# MCU_USB.net
KiCad netlist of a schematic drawn in Altium Designer
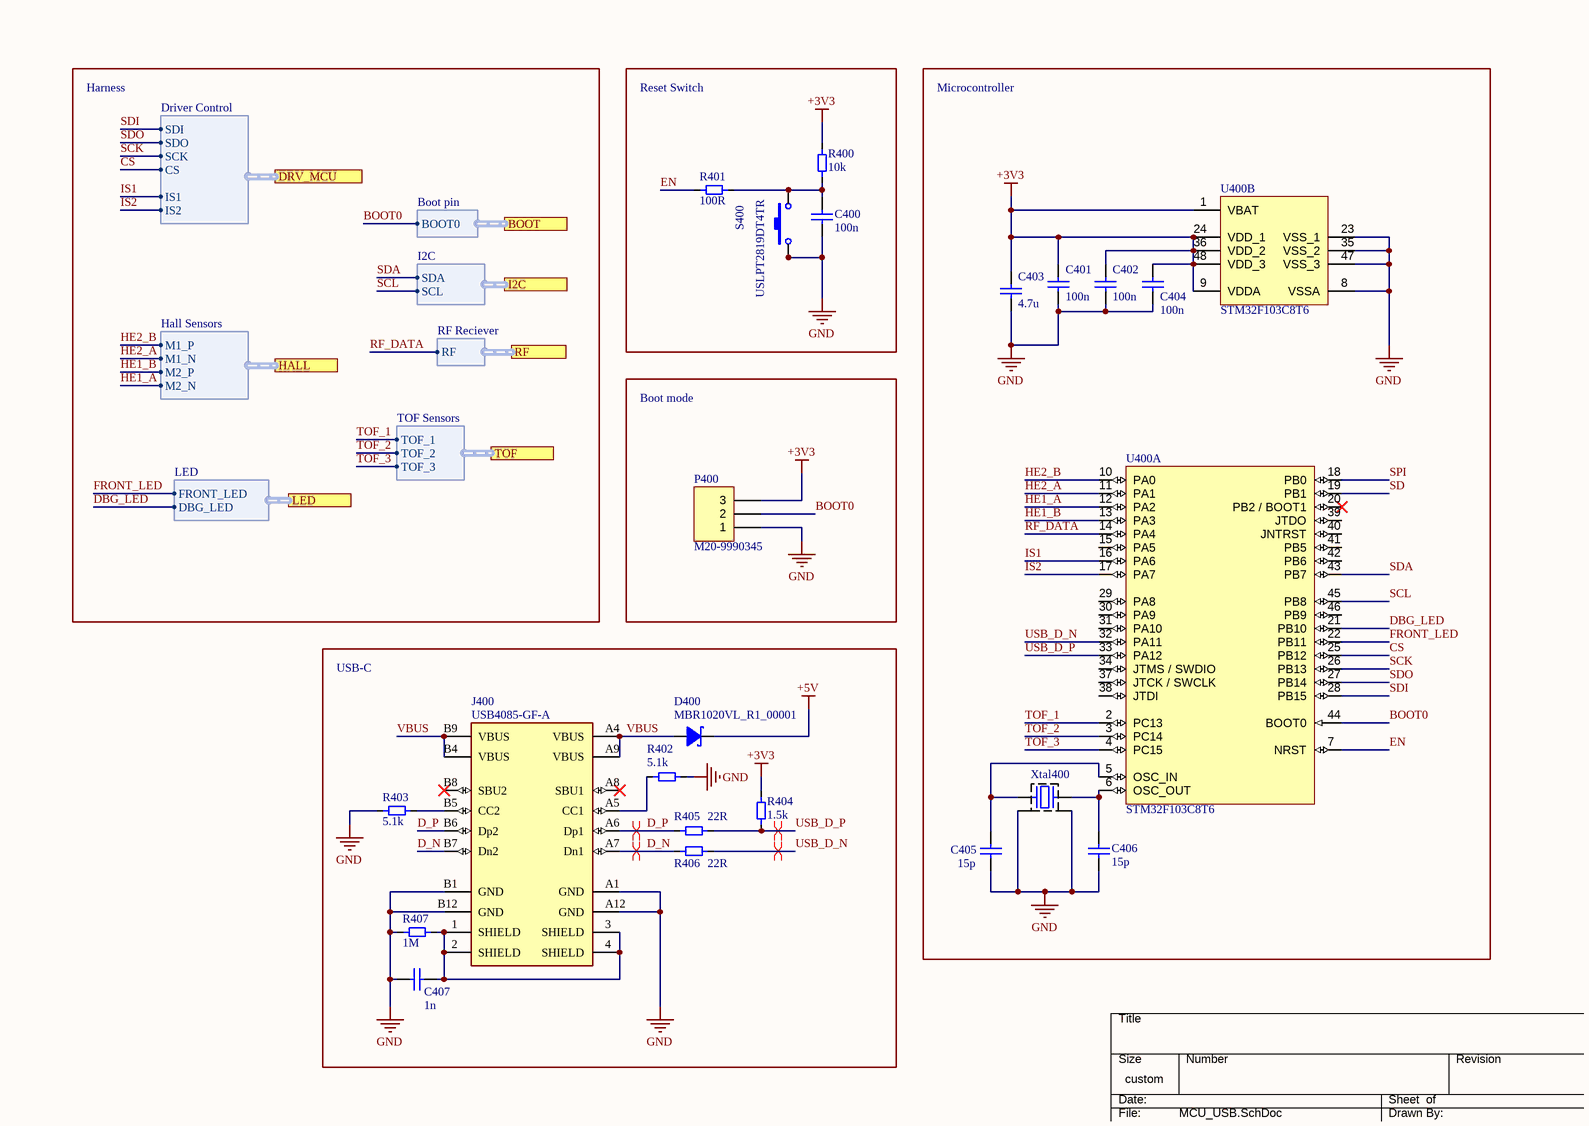
[diagram p0: MCU_USB.SchDoc]

(export (version "E")
  (design (tool "Eeschema 10.0.6"))
  (components
    (comp (ref "C400")
      (value "100n")
      (footprint "MLCC_0603_M")
      (description "MLCC, 0603, 100n, 10%, 50V, X7R")
      (fields (field (name "VOLTAGE") "50V") (field (name "TOLERANCE") "10%"))
      (libsource (lib "Krakul Vault") (part "CAPACITOR_NONPOL_IEC"))
    )
    (comp (ref "C401")
      (value "100n")
      (footprint "MLCC_0603_M")
      (description "MLCC, 0603, 100n, 10%, 50V, X7R")
      (fields (field (name "VOLTAGE") "50V") (field (name "TOLERANCE") "10%"))
      (libsource (lib "Krakul Vault") (part "CAPACITOR_NONPOL_IEC"))
    )
    (comp (ref "C402")
      (value "100n")
      (footprint "MLCC_0603_M")
      (description "MLCC, 0603, 100n, 10%, 50V, X7R")
      (fields (field (name "VOLTAGE") "50V") (field (name "TOLERANCE") "10%"))
      (libsource (lib "Krakul Vault") (part "CAPACITOR_NONPOL_IEC"))
    )
    (comp (ref "C403")
      (value "4.7u")
      (footprint "MLCC_0805_M")
      (description "MLCC, 0805, 4.7u, 20%, 50V, X5R")
      (fields (field (name "MANUFACTURER") "Any") (field (name "VOLTAGE") "50V"))
      (libsource (lib "Krakul Vault") (part "CAPACITOR_NONPOL_IEC"))
    )
    (comp (ref "C404")
      (value "100n")
      (footprint "MLCC_0603_M")
      (description "MLCC, 0603, 100n, 10%, 50V, X7R")
      (fields (field (name "VOLTAGE") "50V") (field (name "TOLERANCE") "10%"))
      (libsource (lib "Krakul Vault") (part "CAPACITOR_NONPOL_IEC"))
    )
    (comp (ref "C405")
      (value "15p")
      (footprint "MLCC_0402_M")
      (description "MLCC, 0402, 15p, 10%, 25V, C0G/NP0")
      (fields (field (name "MANUFACTURER") "Any") (field (name "TOLERANCE") "10%"))
      (libsource (lib "Krakul Vault") (part "CAPACITOR_NONPOL_IEC"))
    )
    (comp (ref "C406")
      (value "15p")
      (footprint "MLCC_0402_M")
      (description "MLCC, 0402, 15p, 10%, 25V, C0G/NP0")
      (fields (field (name "MANUFACTURER") "Any") (field (name "TOLERANCE") "10%"))
      (libsource (lib "Krakul Vault") (part "CAPACITOR_NONPOL_IEC"))
    )
    (comp (ref "C407")
      (value "1n")
      (footprint "MLCC_0603_M")
      (description "MLCC, 0603, 1n, 10%, 50V, X5R")
      (fields (field (name "MANUFACTURER") "Any") (field (name "TOLERANCE") "10%"))
      (libsource (lib "Krakul Vault") (part "CAPACITOR_NONPOL_IEC"))
    )
    (comp (ref "D400")
      (value "MBR1020VL_R1_00001")
      (footprint "FP-MBR1020VL_R1_00001-MFG")
      (description "Rectifier Diode, Schottky, 1 Phase, 1 Element, 1A, 20V V(RRM), Silicon")
      (fields (field (name "MANUFACTURER") "Panjit"))
      (libsource (lib "Krakul Vault") (part "Schottky generic 2 pins"))
    )
    (comp (ref "J400")
      (value "USB4085-GF-A")
      (footprint "FP-USB4085-GF-A-MFG")
      (description "USB Connector, 16 Contact(s), Female, Right Angle, Solder Terminal, Locking, Receptacle")
      (fields (field (name "MANUFACTURER") "GCT") (field (name "PART NUMBER") "USB4800-03-A"))
      (libsource (lib "Krakul Vault") (part "USB4085-GF-A"))
    )
    (comp (ref "P400")
      (value "M20-9990345")
      (footprint "3Pos Pin Header")
      (description "Connector Header Through Hole 3 position 0.100\" (2.54mm)")
      (fields (field (name "MANUFACTURER") "Harwin Inc."))
      (libsource (lib "Krakul Vault") (part "3 pin header"))
    )
    (comp (ref "R400")
      (value "10k")
      (footprint "Resistor_0603_M")
      (description "Resistor, 0603, 10k, 1%, 1/10W")
      (fields (field (name "MANUFACTURER") "Any") (field (name "TOLERANCE") "1%"))
      (libsource (lib "Krakul Vault") (part "RESISTOR_GENERIC_IEC"))
    )
    (comp (ref "R401")
      (value "100R")
      (footprint "Resistor_0603_M")
      (description "Resistor, 0603, 100R, 1%, 1/10W")
      (fields (field (name "POWER") "100mW") (field (name "MANUFACTURER") "Any"))
      (libsource (lib "Krakul Vault") (part "RESISTOR_GENERIC_IEC"))
    )
    (comp (ref "R402")
      (value "5.1k")
      (footprint "Resistor_0603_M")
      (description "Resistor, 0603, 5.1k, 1%, 1/10W")
      (fields (field (name "POWER") "100mW") (field (name "MANUFACTURER") "Any"))
      (libsource (lib "Krakul Vault") (part "RESISTOR_GENERIC_IEC"))
    )
    (comp (ref "R403")
      (value "5.1k")
      (footprint "Resistor_0603_M")
      (description "Resistor, 0603, 5.1k, 1%, 1/10W")
      (fields (field (name "POWER") "100mW") (field (name "MANUFACTURER") "Any"))
      (libsource (lib "Krakul Vault") (part "RESISTOR_GENERIC_IEC"))
    )
    (comp (ref "R404")
      (value "1.5k")
      (footprint "Resistor_0603_M")
      (description "Resistor, 0603, 1.5k, 1%, 1/10W")
      (fields (field (name "MANUFACTURER") "Any") (field (name "POWER") "100mW"))
      (libsource (lib "Krakul Vault") (part "RESISTOR_GENERIC_IEC"))
    )
    (comp (ref "R405")
      (value "22R")
      (footprint "Resistor_0603_M")
      (description "Resistor, 0603, 22R, 1%, 1/10W")
      (fields (field (name "TOLERANCE") "1%") (field (name "MANUFACTURER") "Any"))
      (libsource (lib "Krakul Vault") (part "RESISTOR_GENERIC_IEC"))
    )
    (comp (ref "R406")
      (value "22R")
      (footprint "Resistor_0603_M")
      (description "Resistor, 0603, 22R, 1%, 1/10W")
      (fields (field (name "TOLERANCE") "1%") (field (name "MANUFACTURER") "Any"))
      (libsource (lib "Krakul Vault") (part "RESISTOR_GENERIC_IEC"))
    )
    (comp (ref "R407")
      (value "1M")
      (footprint "Resistor_1206_M")
      (description "Resistor, 1206, 1M, 1%, 1/4W")
      (fields (field (name "MANUFACTURER") "Any"))
      (libsource (lib "Krakul Vault") (part "RESISTOR_GENERIC_IEC"))
    )
    (comp (ref "S400")
      (value "USLPT2819DT4TR")
      (footprint "USLPT2819DT4TR-Footprint-1")
      (description "Keypad Switch, SPST, 0.05A, 1.96N, Solder Terminal, Panel Mount")
      (fields (field (name "MANUFACTURER") "TE Connectivity ALCOSWITCH Switches"))
      (libsource (lib "Krakul Vault") (part "Copy of Switch 4-pin"))
    )
    (comp (ref "U400")
      (value "STM32F103C8T6")
      (footprint "STM-LQFP48_M")
      (description "MCU 32-bit STM32F1 ARM Cortex M3 RISC 64KB Flash 2.5V/3.3V 48-Pin LQFP Tray")
      (fields (field (name "MANUFACTURER") "STMicroelectronics"))
      (libsource (lib "Krakul Vault") (part "MC-ARM-STM32F103X4_6-SQ48"))
    )
    (comp (ref "Xtal400")
      (value "ABM11-16.000MHZ-12-N1G-T")
      (footprint "FP-ABM11-MFG")
      (description "Crystal 16MHz ±10ppm (Tol) ±15ppm (Stability) 12pF FUND 150Ohm 4-Pin Ultra Mini-CSMD T/R")
      (fields (field (name "MANUFACTURER") "Abracon LLC") (field (name "TOLERANCE") "0.001%"))
      (libsource (lib "Krakul Vault") (part "Crystal 4 pins"))
    )
  )
  (nets
    (net (code "12") (name "+3V3") (class "Default")
      (node (ref "C401") (pin "1") (pinfunction "1_1") (pintype "passive"))
      (node (ref "C402") (pin "1") (pinfunction "1_1") (pintype "passive"))
      (node (ref "C403") (pin "2") (pinfunction "2_2") (pintype "passive"))
      (node (ref "C404") (pin "1") (pinfunction "1_1") (pintype "passive"))
      (node (ref "P400") (pin "3") (pinfunction "3_3") (pintype "passive"))
      (node (ref "R400") (pin "2") (pinfunction "2_2") (pintype "passive"))
      (node (ref "R404") (pin "2") (pinfunction "2_2") (pintype "passive"))
      (node (ref "U400") (pin "1") (pinfunction "VBAT_1") (pintype "power_in"))
      (node (ref "U400") (pin "24") (pinfunction "VDD_1_24") (pintype "power_in"))
      (node (ref "U400") (pin "36") (pinfunction "VDD_2_36") (pintype "power_in"))
      (node (ref "U400") (pin "48") (pinfunction "VDD_3_48") (pintype "power_in"))
      (node (ref "U400") (pin "9") (pinfunction "VDDA_9") (pintype "power_in"))
    )
    (net (code "13") (name "+5V") (class "Default")
      (node (ref "D400") (pin "1") (pinfunction "C_1") (pintype "passive"))
    )
    (net (code "14") (name "/BOOT0") (class "Default")
      (node (ref "P400") (pin "2") (pinfunction "2_2") (pintype "passive"))
      (node (ref "U400") (pin "44") (pinfunction "BOOT0_44") (pintype "input"))
    )
    (net (code "15") (name "/CS") (class "Default")
      (node (ref "U400") (pin "25") (pinfunction "PB12_25") (pintype "bidirectional"))
    )
    (net (code "16") (name "/DBG_LED") (class "Default")
      (node (ref "U400") (pin "21") (pinfunction "PB10_21") (pintype "bidirectional"))
    )
    (net (code "17") (name "/D_N") (class "Default")
      (node (ref "J400") (pin "A7") (pinfunction "Dn1_A7") (pintype "bidirectional"))
      (node (ref "J400") (pin "B7") (pinfunction "Dn2_B7") (pintype "bidirectional"))
      (node (ref "R406") (pin "1") (pinfunction "1_1") (pintype "passive"))
    )
    (net (code "18") (name "/D_P") (class "Default")
      (node (ref "J400") (pin "A6") (pinfunction "Dp1_A6") (pintype "bidirectional"))
      (node (ref "J400") (pin "B6") (pinfunction "Dp2_B6") (pintype "bidirectional"))
      (node (ref "R405") (pin "1") (pinfunction "1_1") (pintype "passive"))
    )
    (net (code "19") (name "/EN") (class "Default")
      (node (ref "R401") (pin "2") (pinfunction "2_2") (pintype "passive"))
      (node (ref "U400") (pin "7") (pinfunction "NRST_7") (pintype "bidirectional"))
    )
    (net (code "20") (name "/FRONT_LED") (class "Default")
      (node (ref "U400") (pin "22") (pinfunction "PB11_22") (pintype "bidirectional"))
    )
    (net (code "21") (name "/HE1_A") (class "Default")
      (node (ref "U400") (pin "12") (pinfunction "PA2_12") (pintype "bidirectional"))
    )
    (net (code "22") (name "/HE1_B") (class "Default")
      (node (ref "U400") (pin "13") (pinfunction "PA3_13") (pintype "bidirectional"))
    )
    (net (code "23") (name "/HE2_A") (class "Default")
      (node (ref "U400") (pin "11") (pinfunction "PA1_11") (pintype "bidirectional"))
    )
    (net (code "24") (name "/HE2_B") (class "Default")
      (node (ref "U400") (pin "10") (pinfunction "PA0_10") (pintype "bidirectional"))
    )
    (net (code "25") (name "/IS1") (class "Default")
      (node (ref "U400") (pin "16") (pinfunction "PA6_16") (pintype "bidirectional"))
    )
    (net (code "26") (name "/IS2") (class "Default")
      (node (ref "U400") (pin "17") (pinfunction "PA7_17") (pintype "bidirectional"))
    )
    (net (code "27") (name "/RF_DATA") (class "Default")
      (node (ref "U400") (pin "14") (pinfunction "PA4_14") (pintype "bidirectional"))
    )
    (net (code "28") (name "/SCK") (class "Default")
      (node (ref "U400") (pin "26") (pinfunction "PB13_26") (pintype "bidirectional"))
    )
    (net (code "29") (name "/SCL") (class "Default")
      (node (ref "U400") (pin "45") (pinfunction "PB8_45") (pintype "bidirectional"))
    )
    (net (code "30") (name "/SD") (class "Default")
      (node (ref "U400") (pin "19") (pinfunction "PB1_19") (pintype "bidirectional"))
    )
    (net (code "31") (name "/SDA") (class "Default")
      (node (ref "U400") (pin "43") (pinfunction "PB7_43") (pintype "bidirectional"))
    )
    (net (code "32") (name "/SDI") (class "Default")
      (node (ref "U400") (pin "28") (pinfunction "PB15_28") (pintype "bidirectional"))
    )
    (net (code "33") (name "/SDO") (class "Default")
      (node (ref "U400") (pin "27") (pinfunction "PB14_27") (pintype "bidirectional"))
    )
    (net (code "34") (name "/SPI") (class "Default")
      (node (ref "U400") (pin "18") (pinfunction "PB0_18") (pintype "bidirectional"))
    )
    (net (code "35") (name "/TOF_1") (class "Default")
      (node (ref "U400") (pin "2") (pinfunction "PC13_2") (pintype "bidirectional"))
    )
    (net (code "36") (name "/TOF_2") (class "Default")
      (node (ref "U400") (pin "3") (pinfunction "PC14_3") (pintype "bidirectional"))
    )
    (net (code "37") (name "/TOF_3") (class "Default")
      (node (ref "U400") (pin "4") (pinfunction "PC15_4") (pintype "bidirectional"))
    )
    (net (code "38") (name "/USB_D_N") (class "Default")
      (node (ref "R406") (pin "2") (pinfunction "2_2") (pintype "passive"))
      (node (ref "U400") (pin "32") (pinfunction "PA11_32") (pintype "bidirectional"))
    )
    (net (code "39") (name "/USB_D_P") (class "Default")
      (node (ref "R404") (pin "1") (pinfunction "1_1") (pintype "passive"))
      (node (ref "R405") (pin "2") (pinfunction "2_2") (pintype "passive"))
      (node (ref "U400") (pin "33") (pinfunction "PA12_33") (pintype "bidirectional"))
    )
    (net (code "40") (name "/VBUS") (class "Default")
      (node (ref "D400") (pin "2") (pinfunction "A_2") (pintype "passive"))
      (node (ref "J400") (pin "A4") (pinfunction "VBUS_A4") (pintype "power_in"))
      (node (ref "J400") (pin "A9") (pinfunction "VBUS_A9") (pintype "power_in"))
      (node (ref "J400") (pin "B4") (pinfunction "VBUS_B4") (pintype "power_in"))
      (node (ref "J400") (pin "B9") (pinfunction "VBUS_B9") (pintype "power_in"))
    )
    (net (code "48") (name "GND") (class "Default")
      (node (ref "C400") (pin "1") (pinfunction "1_1") (pintype "passive"))
      (node (ref "C401") (pin "2") (pinfunction "2_2") (pintype "passive"))
      (node (ref "C402") (pin "2") (pinfunction "2_2") (pintype "passive"))
      (node (ref "C403") (pin "1") (pinfunction "1_1") (pintype "passive"))
      (node (ref "C404") (pin "2") (pinfunction "2_2") (pintype "passive"))
      (node (ref "C405") (pin "1") (pinfunction "1_1") (pintype "passive"))
      (node (ref "C406") (pin "1") (pinfunction "1_1") (pintype "passive"))
      (node (ref "C407") (pin "1") (pinfunction "1_1") (pintype "passive"))
      (node (ref "J400") (pin "A1") (pinfunction "GND_A1") (pintype "power_in"))
      (node (ref "J400") (pin "A12") (pinfunction "GND_A12") (pintype "power_in"))
      (node (ref "J400") (pin "B1") (pinfunction "GND_B1") (pintype "power_in"))
      (node (ref "J400") (pin "B12") (pinfunction "GND_B12") (pintype "power_in"))
      (node (ref "P400") (pin "1") (pinfunction "1_1") (pintype "passive"))
      (node (ref "R402") (pin "2") (pinfunction "2_2") (pintype "passive"))
      (node (ref "R403") (pin "1") (pinfunction "1_1") (pintype "passive"))
      (node (ref "R407") (pin "2") (pinfunction "2_2") (pintype "passive"))
      (node (ref "S400") (pin "1") (pinfunction "1_1") (pintype "passive"))
      (node (ref "S400") (pin "2") (pinfunction "2_2") (pintype "passive"))
      (node (ref "U400") (pin "23") (pinfunction "VSS_1_23") (pintype "power_in"))
      (node (ref "U400") (pin "35") (pinfunction "VSS_2_35") (pintype "power_in"))
      (node (ref "U400") (pin "47") (pinfunction "VSS_3_47") (pintype "power_in"))
      (node (ref "U400") (pin "8") (pinfunction "VSSA_8") (pintype "power_in"))
      (node (ref "Xtal400") (pin "2") (pinfunction "2_2") (pintype "power_in"))
      (node (ref "Xtal400") (pin "4") (pinfunction "4_4") (pintype "power_in"))
    )
    (net (code "49") (name "Net-(C400-Pad2)") (class "Default")
      (node (ref "C400") (pin "2") (pinfunction "2_2") (pintype "passive"))
      (node (ref "R400") (pin "1") (pinfunction "1_1") (pintype "passive"))
      (node (ref "R401") (pin "1") (pinfunction "1_1") (pintype "passive"))
      (node (ref "S400") (pin "3") (pinfunction "3_3") (pintype "passive"))
      (node (ref "S400") (pin "4") (pinfunction "4_4") (pintype "passive"))
    )
    (net (code "50") (name "Net-(C407-Pad2)") (class "Default")
      (node (ref "C407") (pin "2") (pinfunction "2_2") (pintype "passive"))
      (node (ref "J400") (pin "1") (pinfunction "SHIELD_1") (pintype "passive"))
      (node (ref "J400") (pin "2") (pinfunction "SHIELD_2") (pintype "passive"))
      (node (ref "J400") (pin "3") (pinfunction "SHIELD_3") (pintype "passive"))
      (node (ref "J400") (pin "4") (pinfunction "SHIELD_4") (pintype "passive"))
      (node (ref "R407") (pin "1") (pinfunction "1_1") (pintype "passive"))
    )
    (net (code "51") (name "Net-(J400-CC1)") (class "Default")
      (node (ref "J400") (pin "A5") (pinfunction "CC1_A5") (pintype "bidirectional"))
      (node (ref "R402") (pin "1") (pinfunction "1_1") (pintype "passive"))
    )
    (net (code "52") (name "Net-(J400-CC2)") (class "Default")
      (node (ref "J400") (pin "B5") (pinfunction "CC2_B5") (pintype "bidirectional"))
      (node (ref "R403") (pin "2") (pinfunction "2_2") (pintype "passive"))
    )
    (net (code "53") (name "Net-(U400A-OSC_IN)") (class "Default")
      (node (ref "C405") (pin "2") (pinfunction "2_2") (pintype "passive"))
      (node (ref "U400") (pin "5") (pinfunction "OSC_IN_5") (pintype "bidirectional"))
      (node (ref "Xtal400") (pin "1") (pinfunction "1_1") (pintype "passive"))
    )
    (net (code "54") (name "Net-(U400A-OSC_OUT)") (class "Default")
      (node (ref "C406") (pin "2") (pinfunction "2_2") (pintype "passive"))
      (node (ref "U400") (pin "6") (pinfunction "OSC_OUT_6") (pintype "bidirectional"))
      (node (ref "Xtal400") (pin "3") (pinfunction "3_3") (pintype "passive"))
    )
    (net (code "55") (name "unconnected-(J400-SBU1-PadA8)") (class "Default")
      (node (ref "J400") (pin "A8") (pinfunction "SBU1_A8") (pintype "bidirectional+no_connect"))
    )
    (net (code "56") (name "unconnected-(J400-SBU2-PadB8)") (class "Default")
      (node (ref "J400") (pin "B8") (pinfunction "SBU2_B8") (pintype "bidirectional+no_connect"))
    )
    (net (code "57") (name "unconnected-(U400A-JNTRST-Pad40)") (class "Default")
      (node (ref "U400") (pin "40") (pinfunction "JNTRST_40") (pintype "bidirectional"))
    )
    (net (code "58") (name "unconnected-(U400A-JTCK_{slash}_SWCLK-Pad37)") (class "Default")
      (node (ref "U400") (pin "37") (pinfunction "JTCK_/_SWCLK_37") (pintype "bidirectional"))
    )
    (net (code "59") (name "unconnected-(U400A-JTDI-Pad38)") (class "Default")
      (node (ref "U400") (pin "38") (pinfunction "JTDI_38") (pintype "bidirectional"))
    )
    (net (code "60") (name "unconnected-(U400A-JTDO-Pad39)") (class "Default")
      (node (ref "U400") (pin "39") (pinfunction "JTDO_39") (pintype "bidirectional"))
    )
    (net (code "61") (name "unconnected-(U400A-JTMS_{slash}_SWDIO-Pad34)") (class "Default")
      (node (ref "U400") (pin "34") (pinfunction "JTMS_/_SWDIO_34") (pintype "bidirectional"))
    )
    (net (code "62") (name "unconnected-(U400A-PA5-Pad15)") (class "Default")
      (node (ref "U400") (pin "15") (pinfunction "PA5_15") (pintype "bidirectional"))
    )
    (net (code "63") (name "unconnected-(U400A-PA8-Pad29)") (class "Default")
      (node (ref "U400") (pin "29") (pinfunction "PA8_29") (pintype "bidirectional"))
    )
    (net (code "64") (name "unconnected-(U400A-PA9-Pad30)") (class "Default")
      (node (ref "U400") (pin "30") (pinfunction "PA9_30") (pintype "bidirectional"))
    )
    (net (code "65") (name "unconnected-(U400A-PA10-Pad31)") (class "Default")
      (node (ref "U400") (pin "31") (pinfunction "PA10_31") (pintype "bidirectional"))
    )
    (net (code "66") (name "unconnected-(U400A-PB2_{slash}_BOOT1-Pad20)") (class "Default")
      (node (ref "U400") (pin "20") (pinfunction "PB2_/_BOOT1_20") (pintype "bidirectional+no_connect"))
    )
    (net (code "67") (name "unconnected-(U400A-PB5-Pad41)") (class "Default")
      (node (ref "U400") (pin "41") (pinfunction "PB5_41") (pintype "bidirectional"))
    )
    (net (code "68") (name "unconnected-(U400A-PB6-Pad42)") (class "Default")
      (node (ref "U400") (pin "42") (pinfunction "PB6_42") (pintype "bidirectional"))
    )
    (net (code "69") (name "unconnected-(U400A-PB9-Pad46)") (class "Default")
      (node (ref "U400") (pin "46") (pinfunction "PB9_46") (pintype "bidirectional"))
    )
  )
)
